# getinline_rev0_unpanaled.net
KiCad netlist of a schematic drawn in EAGLE
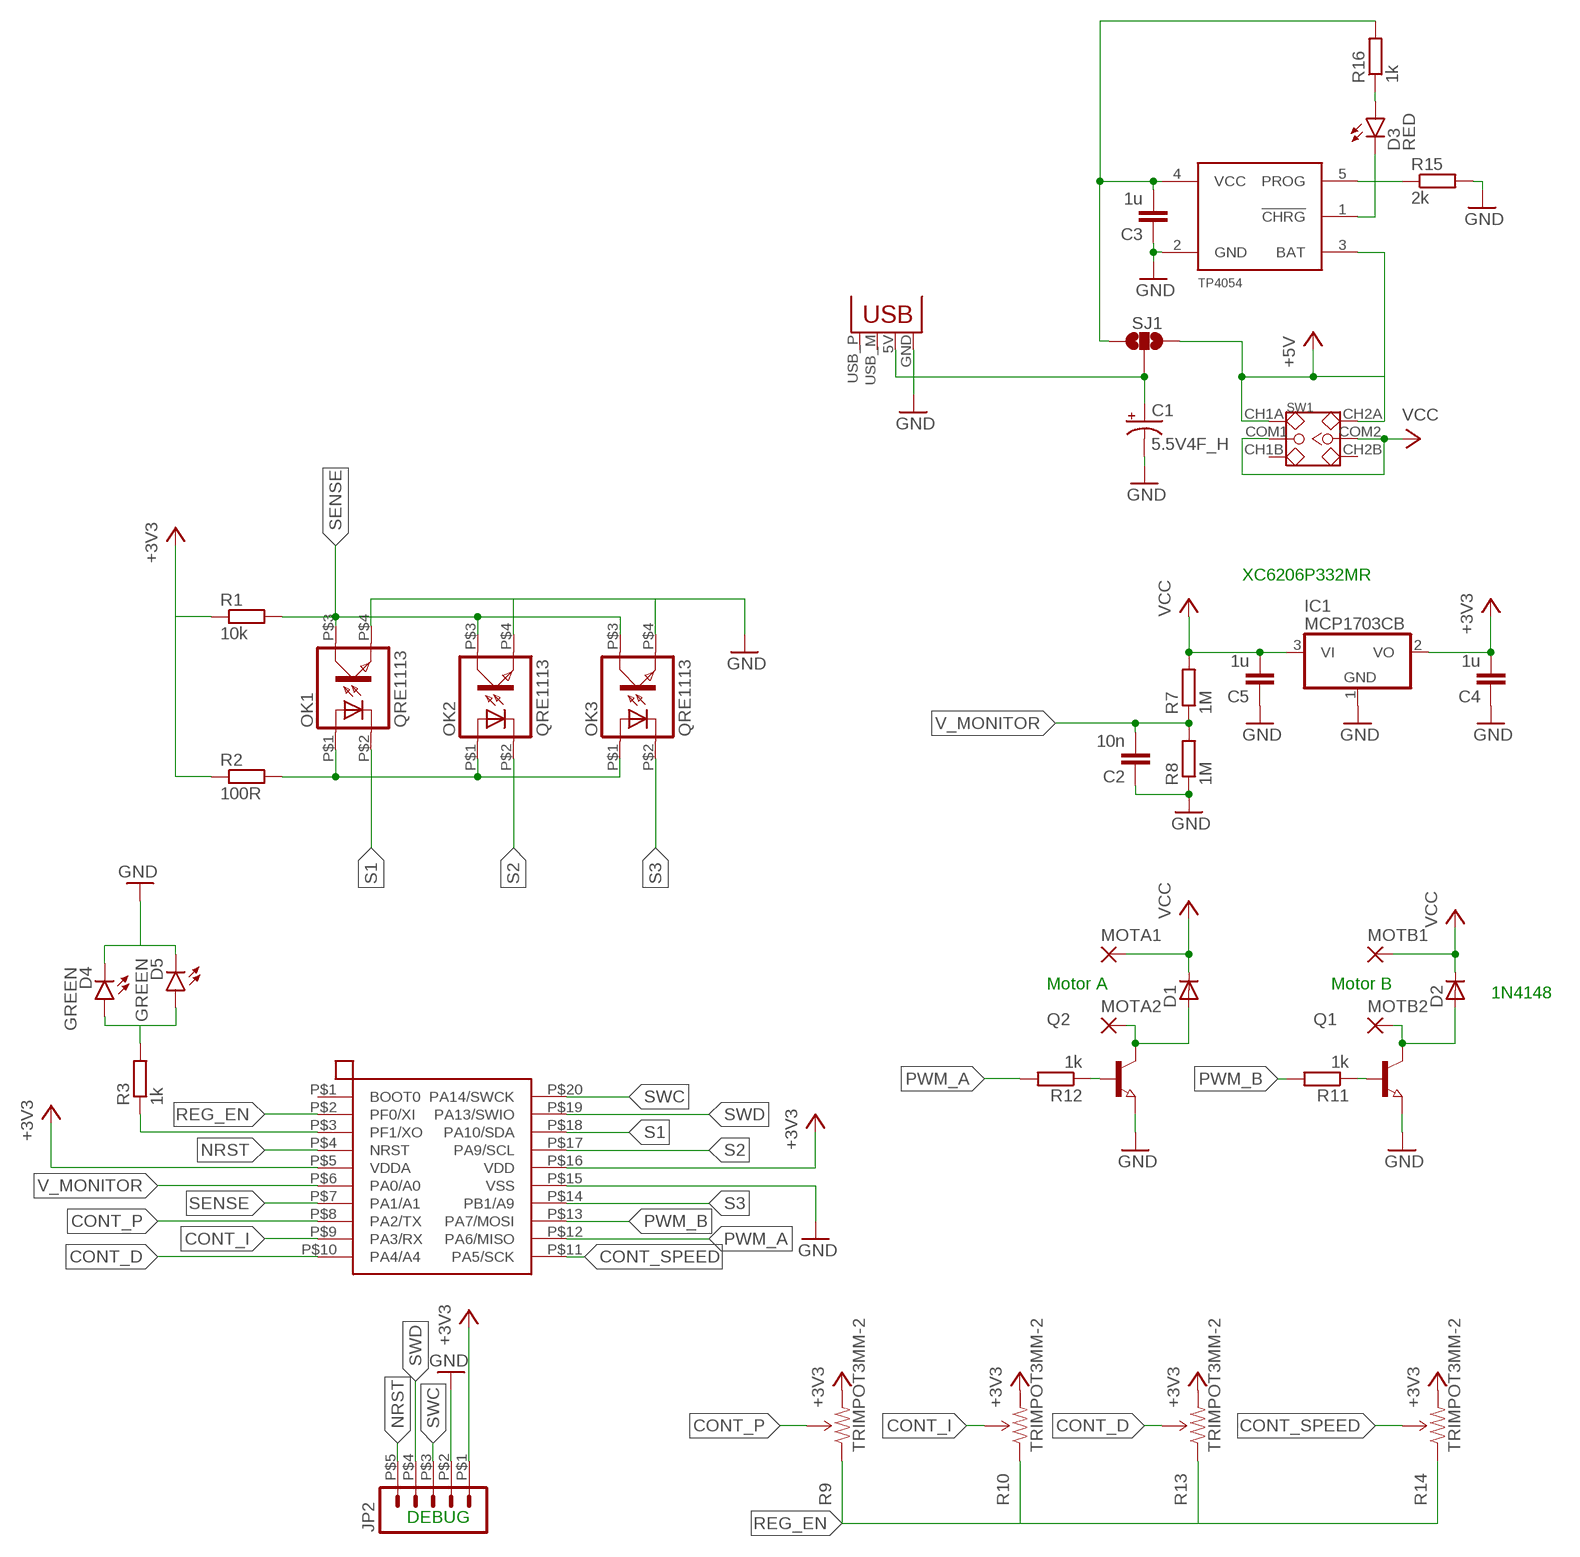
[diagram p0: schematic, sheet 1]

(export (version "E")
  (design (tool "Eeschema 10.0.6"))
  (components
    (comp (ref "C1")
      (value "5.5V4F_H")
      (footprint "eagle-import:5.5V4F_H")
      (libsource (lib "eagle-import") (part "5.5V4F_H"))
    )
    (comp (ref "C2")
      (value "10n")
      (footprint "eagle-import:C0805")
      (libsource (lib "eagle-import") (part "C-EUC0805"))
    )
    (comp (ref "C3")
      (value "1u")
      (footprint "eagle-import:C0805")
      (libsource (lib "eagle-import") (part "C-EUC0805"))
    )
    (comp (ref "C4")
      (value "1u")
      (footprint "eagle-import:C0805")
      (libsource (lib "eagle-import") (part "C-EUC0805"))
    )
    (comp (ref "C5")
      (value "1u")
      (footprint "eagle-import:C0805")
      (libsource (lib "eagle-import") (part "C-EUC0805"))
    )
    (comp (ref "D1")
      (value "D-SOD-80")
      (footprint "eagle-import:SOD80")
      (libsource (lib "eagle-import") (part "D-SOD-80"))
    )
    (comp (ref "D2")
      (value "D-SOD-80")
      (footprint "eagle-import:SOD80")
      (libsource (lib "eagle-import") (part "D-SOD-80"))
    )
    (comp (ref "D3")
      (value "RED")
      (footprint "eagle-import:LED-1206")
      (libsource (lib "eagle-import") (part "LED-RED1206"))
    )
    (comp (ref "D4")
      (value "GREEN")
      (footprint "eagle-import:LED-1206")
      (libsource (lib "eagle-import") (part "LED-GREENLARGE"))
    )
    (comp (ref "D5")
      (value "GREEN")
      (footprint "eagle-import:LED-1206")
      (libsource (lib "eagle-import") (part "LED-GREENLARGE"))
    )
    (comp (ref "IC1")
      (value "MCP1703CB")
      (footprint "eagle-import:SOT23")
      (libsource (lib "eagle-import") (part "MCP1703CB"))
    )
    (comp (ref "JP1")
      (value "USBPCB")
      (footprint "eagle-import:USB-A-PCB")
      (libsource (lib "eagle-import") (part "USBPCB"))
    )
    (comp (ref "JP2")
      (value "M05")
      (footprint "eagle-import:SMD_HEADER_5P")
      (libsource (lib "eagle-import") (part "M05"))
    )
    (comp (ref "MCU")
      (value "STM32F030F4P6")
      (footprint "eagle-import:TSSOP-20")
      (libsource (lib "eagle-import") (part "STM32F030F4P6"))
    )
    (comp (ref "MOTA1")
      (value "1,6/0,9")
      (footprint "eagle-import:1,6_0,9")
      (libsource (lib "eagle-import") (part "1,6/0,9"))
    )
    (comp (ref "MOTA2")
      (value "1,6/0,9")
      (footprint "eagle-import:1,6_0,9")
      (libsource (lib "eagle-import") (part "1,6/0,9"))
    )
    (comp (ref "MOTB1")
      (value "1,6/0,9")
      (footprint "eagle-import:1,6_0,9")
      (libsource (lib "eagle-import") (part "1,6/0,9"))
    )
    (comp (ref "MOTB2")
      (value "1,6/0,9")
      (footprint "eagle-import:1,6_0,9")
      (libsource (lib "eagle-import") (part "1,6/0,9"))
    )
    (comp (ref "OK1")
      (value "QRE1113")
      (footprint "eagle-import:DIL04")
      (libsource (lib "eagle-import") (part "QRE1113"))
    )
    (comp (ref "OK2")
      (value "QRE1113")
      (footprint "eagle-import:DIL04")
      (libsource (lib "eagle-import") (part "QRE1113"))
    )
    (comp (ref "OK3")
      (value "QRE1113")
      (footprint "eagle-import:DIL04")
      (libsource (lib "eagle-import") (part "QRE1113"))
    )
    (comp (ref "Q1")
      (value "NPN-TRANSISTOR_SOT23")
      (footprint "eagle-import:SOT23")
      (libsource (lib "eagle-import") (part "NPN-TRANSISTOR_SOT23"))
    )
    (comp (ref "Q2")
      (value "NPN-TRANSISTOR_SOT23")
      (footprint "eagle-import:SOT23")
      (libsource (lib "eagle-import") (part "NPN-TRANSISTOR_SOT23"))
    )
    (comp (ref "R1")
      (value "10k")
      (footprint "eagle-import:R0805")
      (libsource (lib "eagle-import") (part "R-EU_R0805"))
    )
    (comp (ref "R2")
      (value "100R")
      (footprint "eagle-import:R0805")
      (libsource (lib "eagle-import") (part "R-EU_R0805"))
    )
    (comp (ref "R3")
      (value "1k")
      (footprint "eagle-import:R0805")
      (libsource (lib "eagle-import") (part "R-EU_R0805"))
    )
    (comp (ref "R7")
      (value "1M")
      (footprint "eagle-import:R0805")
      (libsource (lib "eagle-import") (part "R-EU_R0805"))
    )
    (comp (ref "R8")
      (value "1M")
      (footprint "eagle-import:R0805")
      (libsource (lib "eagle-import") (part "R-EU_R0805"))
    )
    (comp (ref "R9")
      (value "TRIMPOT3MM-2")
      (footprint "eagle-import:TRIMPOT-3MM-2")
      (libsource (lib "eagle-import") (part "TRIMPOT3MM-2"))
    )
    (comp (ref "R10")
      (value "TRIMPOT3MM-2")
      (footprint "eagle-import:TRIMPOT-3MM-2")
      (libsource (lib "eagle-import") (part "TRIMPOT3MM-2"))
    )
    (comp (ref "R11")
      (value "1k")
      (footprint "eagle-import:R0805")
      (libsource (lib "eagle-import") (part "R-EU_R0805"))
    )
    (comp (ref "R12")
      (value "1k")
      (footprint "eagle-import:R0805")
      (libsource (lib "eagle-import") (part "R-EU_R0805"))
    )
    (comp (ref "R13")
      (value "TRIMPOT3MM-2")
      (footprint "eagle-import:TRIMPOT-3MM-2")
      (libsource (lib "eagle-import") (part "TRIMPOT3MM-2"))
    )
    (comp (ref "R14")
      (value "TRIMPOT3MM-2")
      (footprint "eagle-import:TRIMPOT-3MM-2")
      (libsource (lib "eagle-import") (part "TRIMPOT3MM-2"))
    )
    (comp (ref "R15")
      (value "2k")
      (footprint "eagle-import:R0805")
      (libsource (lib "eagle-import") (part "R-EU_R0805"))
    )
    (comp (ref "R16")
      (value "1k")
      (footprint "eagle-import:R0805")
      (libsource (lib "eagle-import") (part "R-EU_R0805"))
    )
    (comp (ref "SJ1")
      (value "JUMPER-PAD-3-NOFULL_BOX_SILK")
      (footprint "eagle-import:PAD-JUMPER-3-NO_YES_SILK_FULL_BOX")
      (libsource (lib "eagle-import") (part "JUMPER-PAD-3-NOFULL_BOX_SILK"))
    )
    (comp (ref "SW1")
      (value "DIP-TOGGLE-SWITCH-2CH-(2X3P-2.54)")
      (footprint "eagle-import:SW6-2.54-9.0X3.5X3.2+2.0MM")
      (fields (field (name "MPN") "MS-22D18 G2 ROHS"))
      (libsource (lib "eagle-import") (part "DIP-TOGGLE-SWITCH-2CH-(2X3P-2.54)"))
    )
    (comp (ref "U$1")
      (value "TP4054_LIPO_CHARGER")
      (footprint "eagle-import:SOT23-5")
      (libsource (lib "eagle-import") (part "TP4054_LIPO_CHARGER"))
    )
  )
  (nets
    (net (code "1") (name "+3V3") (class "Default")
      (node (ref "C4") (pin "2") (pinfunction "2_2") (pintype "passive"))
      (node (ref "IC1") (pin "2") (pinfunction "VO_2") (pintype "passive"))
      (node (ref "JP2") (pin "P$1") (pinfunction "1_P$1") (pintype "passive"))
      (node (ref "MCU") (pin "P$16") (pinfunction "VDD_P$16") (pintype "bidirectional"))
      (node (ref "MCU") (pin "P$5") (pinfunction "VDDA_P$5") (pintype "bidirectional"))
      (node (ref "R1") (pin "1") (pinfunction "1_1") (pintype "passive"))
      (node (ref "R10") (pin "3") (pinfunction "CW_3") (pintype "passive"))
      (node (ref "R13") (pin "3") (pinfunction "CW_3") (pintype "passive"))
      (node (ref "R14") (pin "3") (pinfunction "CW_3") (pintype "passive"))
      (node (ref "R2") (pin "1") (pinfunction "1_1") (pintype "passive"))
      (node (ref "R9") (pin "3") (pinfunction "CW_3") (pintype "passive"))
    )
    (net (code "2") (name "+5V") (class "Default")
      (node (ref "SJ1") (pin "3") (pinfunction "3_3") (pintype "passive"))
      (node (ref "SW1") (pin "CH1A") (pinfunction "CH1A_CH1A") (pintype "bidirectional"))
      (node (ref "SW1") (pin "CH2A") (pinfunction "CH2A_CH2A") (pintype "bidirectional"))
      (node (ref "U$1") (pin "3") (pinfunction "BAT_3") (pintype "bidirectional"))
    )
    (net (code "3") (name "CONT_D") (class "Default")
      (node (ref "MCU") (pin "P$10") (pinfunction "PA4/A4_P$10") (pintype "bidirectional"))
      (node (ref "R13") (pin "2") (pinfunction "WIPER_2") (pintype "passive"))
    )
    (net (code "4") (name "CONT_I") (class "Default")
      (node (ref "MCU") (pin "P$9") (pinfunction "PA3/RX_P$9") (pintype "bidirectional"))
      (node (ref "R10") (pin "2") (pinfunction "WIPER_2") (pintype "passive"))
    )
    (net (code "5") (name "CONT_P") (class "Default")
      (node (ref "MCU") (pin "P$8") (pinfunction "PA2/TX_P$8") (pintype "bidirectional"))
      (node (ref "R9") (pin "2") (pinfunction "WIPER_2") (pintype "passive"))
    )
    (net (code "6") (name "CONT_SPEED") (class "Default")
      (node (ref "MCU") (pin "P$11") (pinfunction "PA5/SCK_P$11") (pintype "bidirectional"))
      (node (ref "R14") (pin "2") (pinfunction "WIPER_2") (pintype "passive"))
    )
    (net (code "7") (name "GND") (class "Default")
      (node (ref "C1") (pin "P$2") (pinfunction "-_P$2") (pintype "passive"))
      (node (ref "C2") (pin "1") (pinfunction "1_1") (pintype "passive"))
      (node (ref "C3") (pin "1") (pinfunction "1_1") (pintype "passive"))
      (node (ref "C4") (pin "1") (pinfunction "1_1") (pintype "passive"))
      (node (ref "C5") (pin "1") (pinfunction "1_1") (pintype "passive"))
      (node (ref "D4") (pin "C") (pinfunction "C_C") (pintype "passive"))
      (node (ref "D5") (pin "C") (pinfunction "C_C") (pintype "passive"))
      (node (ref "IC1") (pin "1") (pinfunction "GND_1") (pintype "passive"))
      (node (ref "JP1") (pin "GND") (pinfunction "GND_GND") (pintype "bidirectional"))
      (node (ref "JP2") (pin "P$2") (pinfunction "2_P$2") (pintype "passive"))
      (node (ref "MCU") (pin "P$15") (pinfunction "VSS_P$15") (pintype "bidirectional"))
      (node (ref "OK1") (pin "P$4") (pinfunction "EMIT_P$4") (pintype "passive"))
      (node (ref "OK2") (pin "P$4") (pinfunction "EMIT_P$4") (pintype "passive"))
      (node (ref "OK3") (pin "P$4") (pinfunction "EMIT_P$4") (pintype "passive"))
      (node (ref "Q1") (pin "2") (pinfunction "E_2") (pintype "passive"))
      (node (ref "Q2") (pin "2") (pinfunction "E_2") (pintype "passive"))
      (node (ref "R15") (pin "2") (pinfunction "2_2") (pintype "passive"))
      (node (ref "R8") (pin "1") (pinfunction "1_1") (pintype "passive"))
      (node (ref "U$1") (pin "2") (pinfunction "GND_2") (pintype "bidirectional"))
    )
    (net (code "8") (name "NRST") (class "Default")
      (node (ref "JP2") (pin "P$5") (pinfunction "5_P$5") (pintype "passive"))
      (node (ref "MCU") (pin "P$4") (pinfunction "NRST_P$4") (pintype "bidirectional"))
    )
    (net (code "9") (name "Net-(C1-+)") (class "Default")
      (node (ref "C1") (pin "P$1") (pinfunction "+_P$1") (pintype "passive"))
      (node (ref "JP1") (pin "5V") (pinfunction "VBUS_5V") (pintype "bidirectional"))
      (node (ref "SJ1") (pin "2") (pinfunction "2_2") (pintype "passive"))
    )
    (net (code "10") (name "Net-(D1-A)") (class "Default")
      (node (ref "D1") (pin "2") (pinfunction "A_2") (pintype "passive"))
      (node (ref "MOTA2") (pin "1") (pinfunction "P_1") (pintype "passive"))
      (node (ref "Q2") (pin "3") (pinfunction "C_3") (pintype "passive"))
    )
    (net (code "11") (name "Net-(D2-A)") (class "Default")
      (node (ref "D2") (pin "2") (pinfunction "A_2") (pintype "passive"))
      (node (ref "MOTB2") (pin "1") (pinfunction "P_1") (pintype "passive"))
      (node (ref "Q1") (pin "3") (pinfunction "C_3") (pintype "passive"))
    )
    (net (code "12") (name "Net-(D3-PadA)") (class "Default")
      (node (ref "D3") (pin "A") (pinfunction "A_A") (pintype "passive"))
      (node (ref "R16") (pin "1") (pinfunction "1_1") (pintype "passive"))
    )
    (net (code "13") (name "Net-(D4-PadA)") (class "Default")
      (node (ref "D4") (pin "A") (pinfunction "A_A") (pintype "passive"))
      (node (ref "D5") (pin "A") (pinfunction "A_A") (pintype "passive"))
      (node (ref "R3") (pin "2") (pinfunction "2_2") (pintype "passive"))
    )
    (net (code "14") (name "Net-(MCU-PF1{slash}XO)") (class "Default")
      (node (ref "MCU") (pin "P$3") (pinfunction "PF1/XO_P$3") (pintype "bidirectional"))
      (node (ref "R3") (pin "1") (pinfunction "1_1") (pintype "passive"))
    )
    (net (code "15") (name "Net-(OK1-A)") (class "Default")
      (node (ref "OK1") (pin "P$1") (pinfunction "A_P$1") (pintype "passive"))
      (node (ref "OK2") (pin "P$1") (pinfunction "A_P$1") (pintype "passive"))
      (node (ref "OK3") (pin "P$1") (pinfunction "A_P$1") (pintype "passive"))
      (node (ref "R2") (pin "2") (pinfunction "2_2") (pintype "passive"))
    )
    (net (code "16") (name "Net-(Q1-B)") (class "Default")
      (node (ref "Q1") (pin "1") (pinfunction "B_1") (pintype "passive"))
      (node (ref "R11") (pin "1") (pinfunction "1_1") (pintype "passive"))
    )
    (net (code "17") (name "Net-(Q2-B)") (class "Default")
      (node (ref "Q2") (pin "1") (pinfunction "B_1") (pintype "passive"))
      (node (ref "R12") (pin "1") (pinfunction "1_1") (pintype "passive"))
    )
    (net (code "18") (name "Net-(U$1-PROG)") (class "Default")
      (node (ref "R15") (pin "1") (pinfunction "1_1") (pintype "passive"))
      (node (ref "U$1") (pin "5") (pinfunction "PROG_5") (pintype "bidirectional"))
    )
    (net (code "19") (name "Net-(U$1-VCC)") (class "Default")
      (node (ref "C3") (pin "2") (pinfunction "2_2") (pintype "passive"))
      (node (ref "R16") (pin "2") (pinfunction "2_2") (pintype "passive"))
      (node (ref "SJ1") (pin "1") (pinfunction "1_1") (pintype "passive"))
      (node (ref "U$1") (pin "4") (pinfunction "VCC_4") (pintype "bidirectional"))
    )
    (net (code "20") (name "Net-(U$1-~{CHRG})") (class "Default")
      (node (ref "D3") (pin "C") (pinfunction "C_C") (pintype "passive"))
      (node (ref "U$1") (pin "1") (pinfunction "~{CHRG}_1") (pintype "bidirectional"))
    )
    (net (code "21") (name "PWM_A") (class "Default")
      (node (ref "MCU") (pin "P$12") (pinfunction "PA6/MISO_P$12") (pintype "bidirectional"))
      (node (ref "R12") (pin "2") (pinfunction "2_2") (pintype "passive"))
    )
    (net (code "22") (name "PWM_B") (class "Default")
      (node (ref "MCU") (pin "P$13") (pinfunction "PA7/MOSI_P$13") (pintype "bidirectional"))
      (node (ref "R11") (pin "2") (pinfunction "2_2") (pintype "passive"))
    )
    (net (code "23") (name "REG_EN") (class "Default")
      (node (ref "MCU") (pin "P$2") (pinfunction "PF0/XI_P$2") (pintype "bidirectional"))
      (node (ref "R10") (pin "1") (pinfunction "CCW_1") (pintype "passive"))
      (node (ref "R13") (pin "1") (pinfunction "CCW_1") (pintype "passive"))
      (node (ref "R14") (pin "1") (pinfunction "CCW_1") (pintype "passive"))
      (node (ref "R9") (pin "1") (pinfunction "CCW_1") (pintype "passive"))
    )
    (net (code "24") (name "S1") (class "Default")
      (node (ref "MCU") (pin "P$18") (pinfunction "PA10/SDA_P$18") (pintype "bidirectional"))
      (node (ref "OK1") (pin "P$2") (pinfunction "C_P$2") (pintype "passive"))
    )
    (net (code "25") (name "S2") (class "Default")
      (node (ref "MCU") (pin "P$17") (pinfunction "PA9/SCL_P$17") (pintype "bidirectional"))
      (node (ref "OK2") (pin "P$2") (pinfunction "C_P$2") (pintype "passive"))
    )
    (net (code "26") (name "S3") (class "Default")
      (node (ref "MCU") (pin "P$14") (pinfunction "PB1/A9_P$14") (pintype "bidirectional"))
      (node (ref "OK3") (pin "P$2") (pinfunction "C_P$2") (pintype "passive"))
    )
    (net (code "27") (name "SENSE") (class "Default")
      (node (ref "MCU") (pin "P$7") (pinfunction "PA1/A1_P$7") (pintype "bidirectional"))
      (node (ref "OK1") (pin "P$3") (pinfunction "COL_P$3") (pintype "passive"))
      (node (ref "OK2") (pin "P$3") (pinfunction "COL_P$3") (pintype "passive"))
      (node (ref "OK3") (pin "P$3") (pinfunction "COL_P$3") (pintype "passive"))
      (node (ref "R1") (pin "2") (pinfunction "2_2") (pintype "passive"))
    )
    (net (code "28") (name "SWC") (class "Default")
      (node (ref "JP2") (pin "P$3") (pinfunction "3_P$3") (pintype "passive"))
      (node (ref "MCU") (pin "P$20") (pinfunction "PA14/SWCK_P$20") (pintype "bidirectional"))
    )
    (net (code "29") (name "SWD") (class "Default")
      (node (ref "JP2") (pin "P$4") (pinfunction "4_P$4") (pintype "passive"))
      (node (ref "MCU") (pin "P$19") (pinfunction "PA13/SWIO_P$19") (pintype "bidirectional"))
    )
    (net (code "30") (name "VCC") (class "Default")
      (node (ref "C5") (pin "2") (pinfunction "2_2") (pintype "passive"))
      (node (ref "D1") (pin "1") (pinfunction "C_1") (pintype "passive"))
      (node (ref "D2") (pin "1") (pinfunction "C_1") (pintype "passive"))
      (node (ref "IC1") (pin "3") (pinfunction "VI_3") (pintype "input"))
      (node (ref "MOTA1") (pin "1") (pinfunction "P_1") (pintype "passive"))
      (node (ref "MOTB1") (pin "1") (pinfunction "P_1") (pintype "passive"))
      (node (ref "R7") (pin "2") (pinfunction "2_2") (pintype "passive"))
      (node (ref "SW1") (pin "COM1") (pinfunction "COM1_COM1") (pintype "bidirectional"))
      (node (ref "SW1") (pin "COM2") (pinfunction "COM2_COM2") (pintype "bidirectional"))
    )
    (net (code "31") (name "V_MONITOR") (class "Default")
      (node (ref "C2") (pin "2") (pinfunction "2_2") (pintype "passive"))
      (node (ref "MCU") (pin "P$6") (pinfunction "PA0/A0_P$6") (pintype "bidirectional"))
      (node (ref "R7") (pin "1") (pinfunction "1_1") (pintype "passive"))
      (node (ref "R8") (pin "2") (pinfunction "2_2") (pintype "passive"))
    )
    (net (code "32") (name "unconnected-(JP1-D+-PadUSB_P)") (class "Default")
      (node (ref "JP1") (pin "USB_P") (pinfunction "D+_USB_P") (pintype "bidirectional"))
    )
    (net (code "33") (name "unconnected-(JP1-D--PadUSB_M)") (class "Default")
      (node (ref "JP1") (pin "USB_M") (pinfunction "D-_USB_M") (pintype "bidirectional"))
    )
    (net (code "34") (name "unconnected-(MCU-BOOT0-PadP$1)") (class "Default")
      (node (ref "MCU") (pin "P$1") (pinfunction "BOOT0_P$1") (pintype "bidirectional"))
    )
    (net (code "35") (name "unconnected-(SW1-PadCH1B)") (class "Default")
      (node (ref "SW1") (pin "CH1B") (pinfunction "CH1B_CH1B") (pintype "bidirectional"))
    )
    (net (code "36") (name "unconnected-(SW1-PadCH2B)") (class "Default")
      (node (ref "SW1") (pin "CH2B") (pinfunction "CH2B_CH2B") (pintype "bidirectional"))
    )
  )
)
